# Discovery.net
KiCad netlist of a schematic drawn in Altium Designer
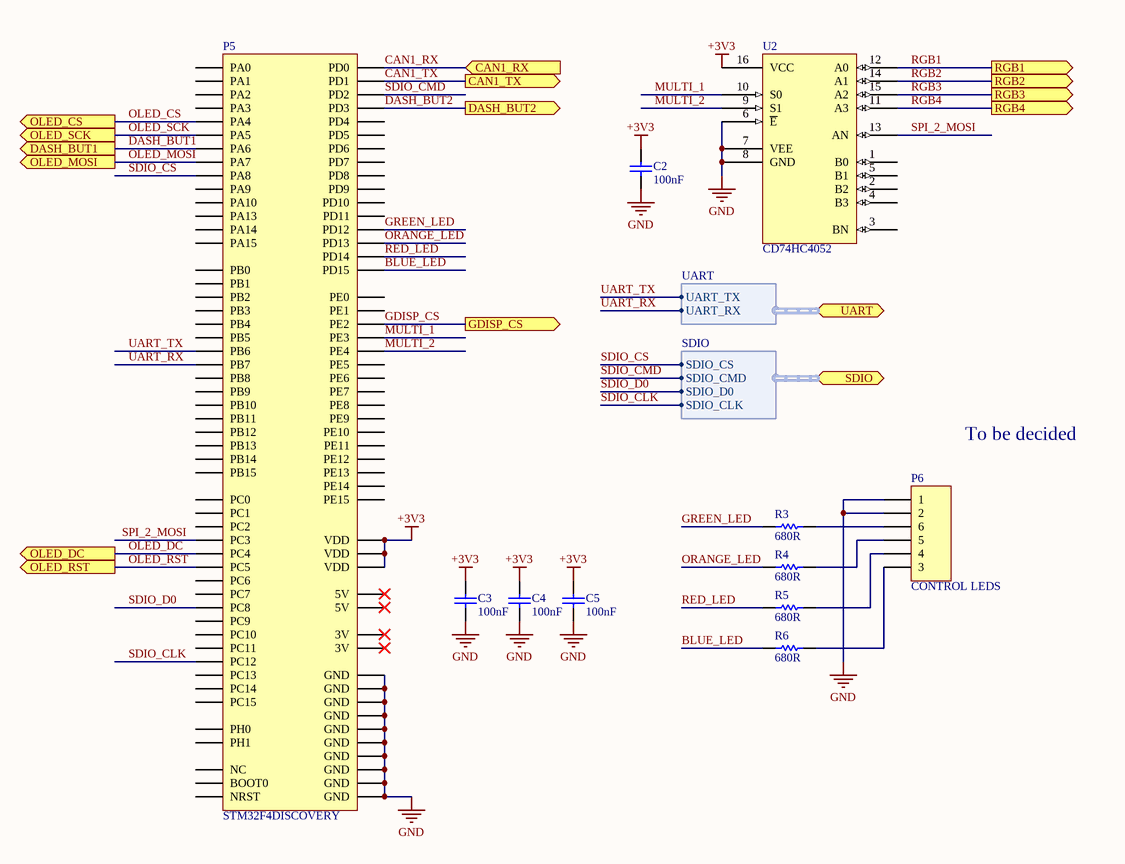
[diagram p0: Discovery.SchDoc]

(export (version "E")
  (design (tool "Eeschema 10.0.6"))
  (components
    (comp (ref "C2")
      (value "100nF")
      (footprint "CAP_0805_IPC_MD")
      (description "Capacitor")
      (fields (field (name "MANUFACTURER") "Samsung") (field (name "Comment") "Cap"))
      (libsource (lib "DataLogger") (part "Cap"))
    )
    (comp (ref "C3")
      (value "100nF")
      (footprint "CAP_0805_IPC_MD")
      (description "Capacitor")
      (fields (field (name "MANUFACTURER") "Samsung") (field (name "Comment") "Cap"))
      (libsource (lib "DataLogger") (part "Cap"))
    )
    (comp (ref "C4")
      (value "100nF")
      (footprint "CAP_0805_IPC_MD")
      (description "Capacitor")
      (fields (field (name "MANUFACTURER") "Samsung") (field (name "Comment") "Cap"))
      (libsource (lib "DataLogger") (part "Cap"))
    )
    (comp (ref "C5")
      (value "100nF")
      (footprint "CAP_0805_IPC_MD")
      (description "Capacitor")
      (fields (field (name "MANUFACTURER") "Samsung") (field (name "Comment") "Cap"))
      (libsource (lib "DataLogger") (part "Cap"))
    )
    (comp (ref "P5")
      (value "STM32F4DISCOVERY")
      (footprint "DISCOVERY_F4")
      (description "STM32F4DISCOVERY connector for shield")
      (fields (field (name "PUBLISHER") "Wojciech Grędel"))
      (libsource (lib "DataLogger") (part "STM32F4DISCOVERY"))
    )
    (comp (ref "P6")
      (value "CONTROL LEDS")
      (footprint "HDR_1x6_3_94_LOCKING")
      (description "Header, 6-Pin")
      (fields (field (name "MANUFACTURER") "Joint Tech") (field (name "PUBLISHER") "Altium Limited"))
      (libsource (lib "DataLogger") (part "Header 6"))
    )
    (comp (ref "R3")
      (value "680R")
      (footprint "RES_0805_IPC_MD")
      (description "Resistor")
      (fields (field (name "Comment") "Res"))
      (libsource (lib "DataLogger") (part "Res"))
    )
    (comp (ref "R4")
      (value "680R")
      (footprint "RES_0805_IPC_MD")
      (description "Resistor")
      (fields (field (name "Comment") "Res"))
      (libsource (lib "DataLogger") (part "Res"))
    )
    (comp (ref "R5")
      (value "680R")
      (footprint "RES_0805_IPC_MD")
      (description "Resistor")
      (fields (field (name "Comment") "Res"))
      (libsource (lib "DataLogger") (part "Res"))
    )
    (comp (ref "R6")
      (value "680R")
      (footprint "RES_0805_IPC_MD")
      (description "Resistor")
      (fields (field (name "Comment") "Res"))
      (libsource (lib "DataLogger") (part "Res"))
    )
    (comp (ref "U2")
      (value "CD74HC4052")
      (footprint "SO_16_IPC_MD")
      (description "MUX/DEMUX")
      (libsource (lib "DataLogger") (part "CD74HC4052"))
    )
  )
  (nets
    (net (code "3") (name "+3V3") (class "Default")
      (node (ref "C2") (pin "2") (pinfunction "2_2") (pintype "passive"))
      (node (ref "C3") (pin "2") (pinfunction "2_2") (pintype "passive"))
      (node (ref "C4") (pin "2") (pinfunction "2_2") (pintype "passive"))
      (node (ref "C5") (pin "2") (pinfunction "2_2") (pintype "passive"))
      (node (ref "P5") (pin "3") (pinfunction "VDD_3") (pintype "power_in"))
      (node (ref "P5") (pin "4") (pinfunction "VDD_4") (pintype "power_in"))
      (node (ref "P5") (pin "72") (pinfunction "VDD_72") (pintype "power_in"))
      (node (ref "U2") (pin "16") (pinfunction "VCC_16") (pintype "passive"))
    )
    (net (code "4") (name "/BLUE_LED") (class "Default")
      (node (ref "P5") (pin "47") (pinfunction "PD15_47") (pintype "passive"))
      (node (ref "R6") (pin "1") (pinfunction "1_1") (pintype "passive"))
    )
    (net (code "5") (name "/CAN1_RX") (class "Default")
      (node (ref "P5") (pin "86") (pinfunction "PD0_86") (pintype "passive"))
    )
    (net (code "6") (name "/CAN1_TX") (class "Default")
      (node (ref "P5") (pin "83") (pinfunction "PD1_83") (pintype "passive"))
    )
    (net (code "7") (name "/DASH_BUT1") (class "Default")
      (node (ref "P5") (pin "18") (pinfunction "PA6_18") (pintype "passive"))
    )
    (net (code "8") (name "/DASH_BUT2") (class "Default")
      (node (ref "P5") (pin "81") (pinfunction "PD3_81") (pintype "passive"))
    )
    (net (code "9") (name "/GDISP_CS") (class "Default")
      (node (ref "P5") (pin "65") (pinfunction "PE2_65") (pintype "passive"))
    )
    (net (code "10") (name "/GREEN_LED") (class "Default")
      (node (ref "P5") (pin "44") (pinfunction "PD12_44") (pintype "passive"))
      (node (ref "R3") (pin "1") (pinfunction "1_1") (pintype "passive"))
    )
    (net (code "11") (name "/MULTI_1") (class "Default")
      (node (ref "P5") (pin "66") (pinfunction "PE3_66") (pintype "passive"))
      (node (ref "U2") (pin "10") (pinfunction "S0_10") (pintype "input"))
    )
    (net (code "12") (name "/MULTI_2") (class "Default")
      (node (ref "P5") (pin "63") (pinfunction "PE4_63") (pintype "passive"))
      (node (ref "U2") (pin "9") (pinfunction "S1_9") (pintype "input"))
    )
    (net (code "13") (name "/OLED_CS") (class "Default")
      (node (ref "P5") (pin "16") (pinfunction "PA4_16") (pintype "passive"))
    )
    (net (code "14") (name "/OLED_DC") (class "Default")
      (node (ref "P5") (pin "20") (pinfunction "PC4_20") (pintype "passive"))
    )
    (net (code "15") (name "/OLED_MOSI") (class "Default")
      (node (ref "P5") (pin "17") (pinfunction "PA7_17") (pintype "passive"))
    )
    (net (code "16") (name "/OLED_RST") (class "Default")
      (node (ref "P5") (pin "19") (pinfunction "PC5_19") (pintype "passive"))
    )
    (net (code "17") (name "/OLED_SCK") (class "Default")
      (node (ref "P5") (pin "15") (pinfunction "PA5_15") (pintype "passive"))
    )
    (net (code "18") (name "/ORANGE_LED") (class "Default")
      (node (ref "P5") (pin "45") (pinfunction "PD13_45") (pintype "passive"))
      (node (ref "R4") (pin "1") (pinfunction "1_1") (pintype "passive"))
    )
    (net (code "19") (name "/RED_LED") (class "Default")
      (node (ref "P5") (pin "46") (pinfunction "PD14_46") (pintype "passive"))
      (node (ref "R5") (pin "1") (pinfunction "1_1") (pintype "passive"))
    )
    (net (code "20") (name "/RGB1") (class "Default")
      (node (ref "U2") (pin "12") (pinfunction "A0_12") (pintype "bidirectional"))
    )
    (net (code "21") (name "/RGB2") (class "Default")
      (node (ref "U2") (pin "14") (pinfunction "A1_14") (pintype "bidirectional"))
    )
    (net (code "22") (name "/RGB3") (class "Default")
      (node (ref "U2") (pin "15") (pinfunction "A2_15") (pintype "bidirectional"))
    )
    (net (code "23") (name "/RGB4") (class "Default")
      (node (ref "U2") (pin "11") (pinfunction "A3_11") (pintype "bidirectional"))
    )
    (net (code "24") (name "/SDIO_CLK") (class "Default")
      (node (ref "P5") (pin "85") (pinfunction "PC12_85") (pintype "passive"))
    )
    (net (code "25") (name "/SDIO_CMD") (class "Default")
      (node (ref "P5") (pin "84") (pinfunction "PD2_84") (pintype "passive"))
    )
    (net (code "26") (name "/SDIO_CS") (class "Default")
      (node (ref "P5") (pin "93") (pinfunction "PA8_93") (pintype "passive"))
    )
    (net (code "27") (name "/SDIO_D0") (class "Default")
      (node (ref "P5") (pin "95") (pinfunction "PC8_95") (pintype "passive"))
    )
    (net (code "28") (name "/SPI_2_MOSI") (class "Default")
      (node (ref "P5") (pin "9") (pinfunction "PC3_9") (pintype "passive"))
      (node (ref "U2") (pin "13") (pinfunction "AN_13") (pintype "bidirectional"))
    )
    (net (code "29") (name "/UART_RX") (class "Default")
      (node (ref "P5") (pin "74") (pinfunction "PB7_74") (pintype "passive"))
    )
    (net (code "30") (name "/UART_TX") (class "Default")
      (node (ref "P5") (pin "73") (pinfunction "PB6_73") (pintype "passive"))
    )
    (net (code "33") (name "GND") (class "Default")
      (node (ref "C2") (pin "1") (pinfunction "1_1") (pintype "passive"))
      (node (ref "C3") (pin "1") (pinfunction "1_1") (pintype "passive"))
      (node (ref "C4") (pin "1") (pinfunction "1_1") (pintype "passive"))
      (node (ref "C5") (pin "1") (pinfunction "1_1") (pintype "passive"))
      (node (ref "P5") (pin "1") (pinfunction "GND_1") (pintype "power_in"))
      (node (ref "P5") (pin "100") (pinfunction "GND_100") (pintype "power_in"))
      (node (ref "P5") (pin "2") (pinfunction "GND_2") (pintype "power_in"))
      (node (ref "P5") (pin "23") (pinfunction "GND_23") (pintype "power_in"))
      (node (ref "P5") (pin "49") (pinfunction "GND_49") (pintype "power_in"))
      (node (ref "P5") (pin "5") (pinfunction "GND_5") (pintype "power_in"))
      (node (ref "P5") (pin "50") (pinfunction "GND_50") (pintype "power_in"))
      (node (ref "P5") (pin "51") (pinfunction "GND_51") (pintype "power_in"))
      (node (ref "P5") (pin "52") (pinfunction "GND_52") (pintype "power_in"))
      (node (ref "P5") (pin "99") (pinfunction "GND_99") (pintype "power_in"))
      (node (ref "P6") (pin "1") (pinfunction "1_1") (pintype "passive"))
      (node (ref "P6") (pin "2") (pinfunction "2_2") (pintype "passive"))
      (node (ref "U2") (pin "6") (pinfunction "~{E}_6") (pintype "input"))
      (node (ref "U2") (pin "7") (pinfunction "VEE_7") (pintype "power_in"))
      (node (ref "U2") (pin "8") (pinfunction "GND_8") (pintype "power_in"))
    )
    (net (code "34") (name "Net-(P6-Pad3)") (class "Default")
      (node (ref "P6") (pin "3") (pinfunction "3_3") (pintype "passive"))
      (node (ref "R6") (pin "2") (pinfunction "2_2") (pintype "passive"))
    )
    (net (code "35") (name "Net-(P6-Pad4)") (class "Default")
      (node (ref "P6") (pin "4") (pinfunction "4_4") (pintype "passive"))
      (node (ref "R5") (pin "2") (pinfunction "2_2") (pintype "passive"))
    )
    (net (code "36") (name "Net-(P6-Pad5)") (class "Default")
      (node (ref "P6") (pin "5") (pinfunction "5_5") (pintype "passive"))
      (node (ref "R4") (pin "2") (pinfunction "2_2") (pintype "passive"))
    )
    (net (code "37") (name "Net-(P6-Pad6)") (class "Default")
      (node (ref "P6") (pin "6") (pinfunction "6_6") (pintype "passive"))
      (node (ref "R3") (pin "2") (pinfunction "2_2") (pintype "passive"))
    )
    (net (code "38") (name "unconnected-(P5-3V-Pad55)") (class "Default")
      (node (ref "P5") (pin "55") (pinfunction "3V_55") (pintype "power_in+no_connect"))
    )
    (net (code "39") (name "unconnected-(P5-3V-Pad56)") (class "Default")
      (node (ref "P5") (pin "56") (pinfunction "3V_56") (pintype "power_in+no_connect"))
    )
    (net (code "40") (name "unconnected-(P5-5V-Pad53)") (class "Default")
      (node (ref "P5") (pin "53") (pinfunction "5V_53") (pintype "power_in+no_connect"))
    )
    (net (code "41") (name "unconnected-(P5-5V-Pad54)") (class "Default")
      (node (ref "P5") (pin "54") (pinfunction "5V_54") (pintype "power_in+no_connect"))
    )
    (net (code "42") (name "unconnected-(P5-BOOT0-Pad71)") (class "Default")
      (node (ref "P5") (pin "71") (pinfunction "BOOT0_71") (pintype "passive"))
    )
    (net (code "43") (name "unconnected-(P5-NC-Pad48)") (class "Default")
      (node (ref "P5") (pin "48") (pinfunction "NC_48") (pintype "passive"))
    )
    (net (code "44") (name "unconnected-(P5-NRST-Pad6)") (class "Default")
      (node (ref "P5") (pin "6") (pinfunction "NRST_6") (pintype "passive"))
    )
    (net (code "45") (name "unconnected-(P5-PA0-Pad12)") (class "Default")
      (node (ref "P5") (pin "12") (pinfunction "PA0_12") (pintype "passive"))
    )
    (net (code "46") (name "unconnected-(P5-PA1-Pad11)") (class "Default")
      (node (ref "P5") (pin "11") (pinfunction "PA1_11") (pintype "passive"))
    )
    (net (code "47") (name "unconnected-(P5-PA2-Pad14)") (class "Default")
      (node (ref "P5") (pin "14") (pinfunction "PA2_14") (pintype "passive"))
    )
    (net (code "48") (name "unconnected-(P5-PA3-Pad13)") (class "Default")
      (node (ref "P5") (pin "13") (pinfunction "PA3_13") (pintype "passive"))
    )
    (net (code "49") (name "unconnected-(P5-PA9-Pad94)") (class "Default")
      (node (ref "P5") (pin "94") (pinfunction "PA9_94") (pintype "passive"))
    )
    (net (code "50") (name "unconnected-(P5-PA10-Pad91)") (class "Default")
      (node (ref "P5") (pin "91") (pinfunction "PA10_91") (pintype "passive"))
    )
    (net (code "51") (name "unconnected-(P5-PA13-Pad92)") (class "Default")
      (node (ref "P5") (pin "92") (pinfunction "PA13_92") (pintype "passive"))
    )
    (net (code "52") (name "unconnected-(P5-PA14-Pad89)") (class "Default")
      (node (ref "P5") (pin "89") (pinfunction "PA14_89") (pintype "passive"))
    )
    (net (code "53") (name "unconnected-(P5-PA15-Pad90)") (class "Default")
      (node (ref "P5") (pin "90") (pinfunction "PA15_90") (pintype "passive"))
    )
    (net (code "54") (name "unconnected-(P5-PB0-Pad22)") (class "Default")
      (node (ref "P5") (pin "22") (pinfunction "PB0_22") (pintype "passive"))
    )
    (net (code "55") (name "unconnected-(P5-PB1-Pad21)") (class "Default")
      (node (ref "P5") (pin "21") (pinfunction "PB1_21") (pintype "passive"))
    )
    (net (code "56") (name "unconnected-(P5-PB2-Pad24)") (class "Default")
      (node (ref "P5") (pin "24") (pinfunction "PB2_24") (pintype "passive"))
    )
    (net (code "57") (name "unconnected-(P5-PB3-Pad78)") (class "Default")
      (node (ref "P5") (pin "78") (pinfunction "PB3_78") (pintype "passive"))
    )
    (net (code "58") (name "unconnected-(P5-PB4-Pad75)") (class "Default")
      (node (ref "P5") (pin "75") (pinfunction "PB4_75") (pintype "passive"))
    )
    (net (code "59") (name "unconnected-(P5-PB5-Pad76)") (class "Default")
      (node (ref "P5") (pin "76") (pinfunction "PB5_76") (pintype "passive"))
    )
    (net (code "60") (name "unconnected-(P5-PB8-Pad69)") (class "Default")
      (node (ref "P5") (pin "69") (pinfunction "PB8_69") (pintype "passive"))
    )
    (net (code "61") (name "unconnected-(P5-PB9-Pad70)") (class "Default")
      (node (ref "P5") (pin "70") (pinfunction "PB9_70") (pintype "passive"))
    )
    (net (code "62") (name "unconnected-(P5-PB10-Pad34)") (class "Default")
      (node (ref "P5") (pin "34") (pinfunction "PB10_34") (pintype "passive"))
    )
    (net (code "63") (name "unconnected-(P5-PB11-Pad35)") (class "Default")
      (node (ref "P5") (pin "35") (pinfunction "PB11_35") (pintype "passive"))
    )
    (net (code "64") (name "unconnected-(P5-PB12-Pad36)") (class "Default")
      (node (ref "P5") (pin "36") (pinfunction "PB12_36") (pintype "passive"))
    )
    (net (code "65") (name "unconnected-(P5-PB13-Pad37)") (class "Default")
      (node (ref "P5") (pin "37") (pinfunction "PB13_37") (pintype "passive"))
    )
    (net (code "66") (name "unconnected-(P5-PB14-Pad38)") (class "Default")
      (node (ref "P5") (pin "38") (pinfunction "PB14_38") (pintype "passive"))
    )
    (net (code "67") (name "unconnected-(P5-PB15-Pad39)") (class "Default")
      (node (ref "P5") (pin "39") (pinfunction "PB15_39") (pintype "passive"))
    )
    (net (code "68") (name "unconnected-(P5-PC0-Pad8)") (class "Default")
      (node (ref "P5") (pin "8") (pinfunction "PC0_8") (pintype "passive"))
    )
    (net (code "69") (name "unconnected-(P5-PC1-Pad7)") (class "Default")
      (node (ref "P5") (pin "7") (pinfunction "PC1_7") (pintype "passive"))
    )
    (net (code "70") (name "unconnected-(P5-PC2-Pad10)") (class "Default")
      (node (ref "P5") (pin "10") (pinfunction "PC2_10") (pintype "passive"))
    )
    (net (code "71") (name "unconnected-(P5-PC6-Pad97)") (class "Default")
      (node (ref "P5") (pin "97") (pinfunction "PC6_97") (pintype "passive"))
    )
    (net (code "72") (name "unconnected-(P5-PC7-Pad98)") (class "Default")
      (node (ref "P5") (pin "98") (pinfunction "PC7_98") (pintype "passive"))
    )
    (net (code "73") (name "unconnected-(P5-PC9-Pad96)") (class "Default")
      (node (ref "P5") (pin "96") (pinfunction "PC9_96") (pintype "passive"))
    )
    (net (code "74") (name "unconnected-(P5-PC10-Pad87)") (class "Default")
      (node (ref "P5") (pin "87") (pinfunction "PC10_87") (pintype "passive"))
    )
    (net (code "75") (name "unconnected-(P5-PC11-Pad88)") (class "Default")
      (node (ref "P5") (pin "88") (pinfunction "PC11_88") (pintype "passive"))
    )
    (net (code "76") (name "unconnected-(P5-PC13-Pad62)") (class "Default")
      (node (ref "P5") (pin "62") (pinfunction "PC13_62") (pintype "passive"))
    )
    (net (code "77") (name "unconnected-(P5-PC14-Pad59)") (class "Default")
      (node (ref "P5") (pin "59") (pinfunction "PC14_59") (pintype "passive"))
    )
    (net (code "78") (name "unconnected-(P5-PC15-Pad60)") (class "Default")
      (node (ref "P5") (pin "60") (pinfunction "PC15_60") (pintype "passive"))
    )
    (net (code "79") (name "unconnected-(P5-PD4-Pad82)") (class "Default")
      (node (ref "P5") (pin "82") (pinfunction "PD4_82") (pintype "passive"))
    )
    (net (code "80") (name "unconnected-(P5-PD5-Pad79)") (class "Default")
      (node (ref "P5") (pin "79") (pinfunction "PD5_79") (pintype "passive"))
    )
    (net (code "81") (name "unconnected-(P5-PD6-Pad80)") (class "Default")
      (node (ref "P5") (pin "80") (pinfunction "PD6_80") (pintype "passive"))
    )
    (net (code "82") (name "unconnected-(P5-PD7-Pad77)") (class "Default")
      (node (ref "P5") (pin "77") (pinfunction "PD7_77") (pintype "passive"))
    )
    (net (code "83") (name "unconnected-(P5-PD8-Pad40)") (class "Default")
      (node (ref "P5") (pin "40") (pinfunction "PD8_40") (pintype "passive"))
    )
    (net (code "84") (name "unconnected-(P5-PD9-Pad41)") (class "Default")
      (node (ref "P5") (pin "41") (pinfunction "PD9_41") (pintype "passive"))
    )
    (net (code "85") (name "unconnected-(P5-PD10-Pad42)") (class "Default")
      (node (ref "P5") (pin "42") (pinfunction "PD10_42") (pintype "passive"))
    )
    (net (code "86") (name "unconnected-(P5-PD11-Pad43)") (class "Default")
      (node (ref "P5") (pin "43") (pinfunction "PD11_43") (pintype "passive"))
    )
    (net (code "87") (name "unconnected-(P5-PE0-Pad67)") (class "Default")
      (node (ref "P5") (pin "67") (pinfunction "PE0_67") (pintype "passive"))
    )
    (net (code "88") (name "unconnected-(P5-PE1-Pad68)") (class "Default")
      (node (ref "P5") (pin "68") (pinfunction "PE1_68") (pintype "passive"))
    )
    (net (code "89") (name "unconnected-(P5-PE5-Pad64)") (class "Default")
      (node (ref "P5") (pin "64") (pinfunction "PE5_64") (pintype "passive"))
    )
    (net (code "90") (name "unconnected-(P5-PE6-Pad61)") (class "Default")
      (node (ref "P5") (pin "61") (pinfunction "PE6_61") (pintype "passive"))
    )
    (net (code "91") (name "unconnected-(P5-PE7-Pad25)") (class "Default")
      (node (ref "P5") (pin "25") (pinfunction "PE7_25") (pintype "passive"))
    )
    (net (code "92") (name "unconnected-(P5-PE8-Pad26)") (class "Default")
      (node (ref "P5") (pin "26") (pinfunction "PE8_26") (pintype "passive"))
    )
    (net (code "93") (name "unconnected-(P5-PE9-Pad27)") (class "Default")
      (node (ref "P5") (pin "27") (pinfunction "PE9_27") (pintype "passive"))
    )
    (net (code "94") (name "unconnected-(P5-PE10-Pad28)") (class "Default")
      (node (ref "P5") (pin "28") (pinfunction "PE10_28") (pintype "passive"))
    )
    (net (code "95") (name "unconnected-(P5-PE11-Pad29)") (class "Default")
      (node (ref "P5") (pin "29") (pinfunction "PE11_29") (pintype "passive"))
    )
    (net (code "96") (name "unconnected-(P5-PE12-Pad30)") (class "Default")
      (node (ref "P5") (pin "30") (pinfunction "PE12_30") (pintype "passive"))
    )
    (net (code "97") (name "unconnected-(P5-PE13-Pad31)") (class "Default")
      (node (ref "P5") (pin "31") (pinfunction "PE13_31") (pintype "passive"))
    )
    (net (code "98") (name "unconnected-(P5-PE14-Pad32)") (class "Default")
      (node (ref "P5") (pin "32") (pinfunction "PE14_32") (pintype "passive"))
    )
    (net (code "99") (name "unconnected-(P5-PE15-Pad33)") (class "Default")
      (node (ref "P5") (pin "33") (pinfunction "PE15_33") (pintype "passive"))
    )
    (net (code "100") (name "unconnected-(P5-PH0-Pad57)") (class "Default")
      (node (ref "P5") (pin "57") (pinfunction "PH0_57") (pintype "passive"))
    )
    (net (code "101") (name "unconnected-(P5-PH1-Pad58)") (class "Default")
      (node (ref "P5") (pin "58") (pinfunction "PH1_58") (pintype "passive"))
    )
    (net (code "102") (name "unconnected-(U2-B0-Pad1)") (class "Default")
      (node (ref "U2") (pin "1") (pinfunction "B0_1") (pintype "bidirectional"))
    )
    (net (code "103") (name "unconnected-(U2-B1-Pad5)") (class "Default")
      (node (ref "U2") (pin "5") (pinfunction "B1_5") (pintype "bidirectional"))
    )
    (net (code "104") (name "unconnected-(U2-B2-Pad2)") (class "Default")
      (node (ref "U2") (pin "2") (pinfunction "B2_2") (pintype "bidirectional"))
    )
    (net (code "105") (name "unconnected-(U2-B3-Pad4)") (class "Default")
      (node (ref "U2") (pin "4") (pinfunction "B3_4") (pintype "bidirectional"))
    )
    (net (code "106") (name "unconnected-(U2-BN-Pad3)") (class "Default")
      (node (ref "U2") (pin "3") (pinfunction "BN_3") (pintype "bidirectional"))
    )
  )
)
